# usb-hub-v0_1.net
KiCad netlist of a schematic drawn in EAGLE
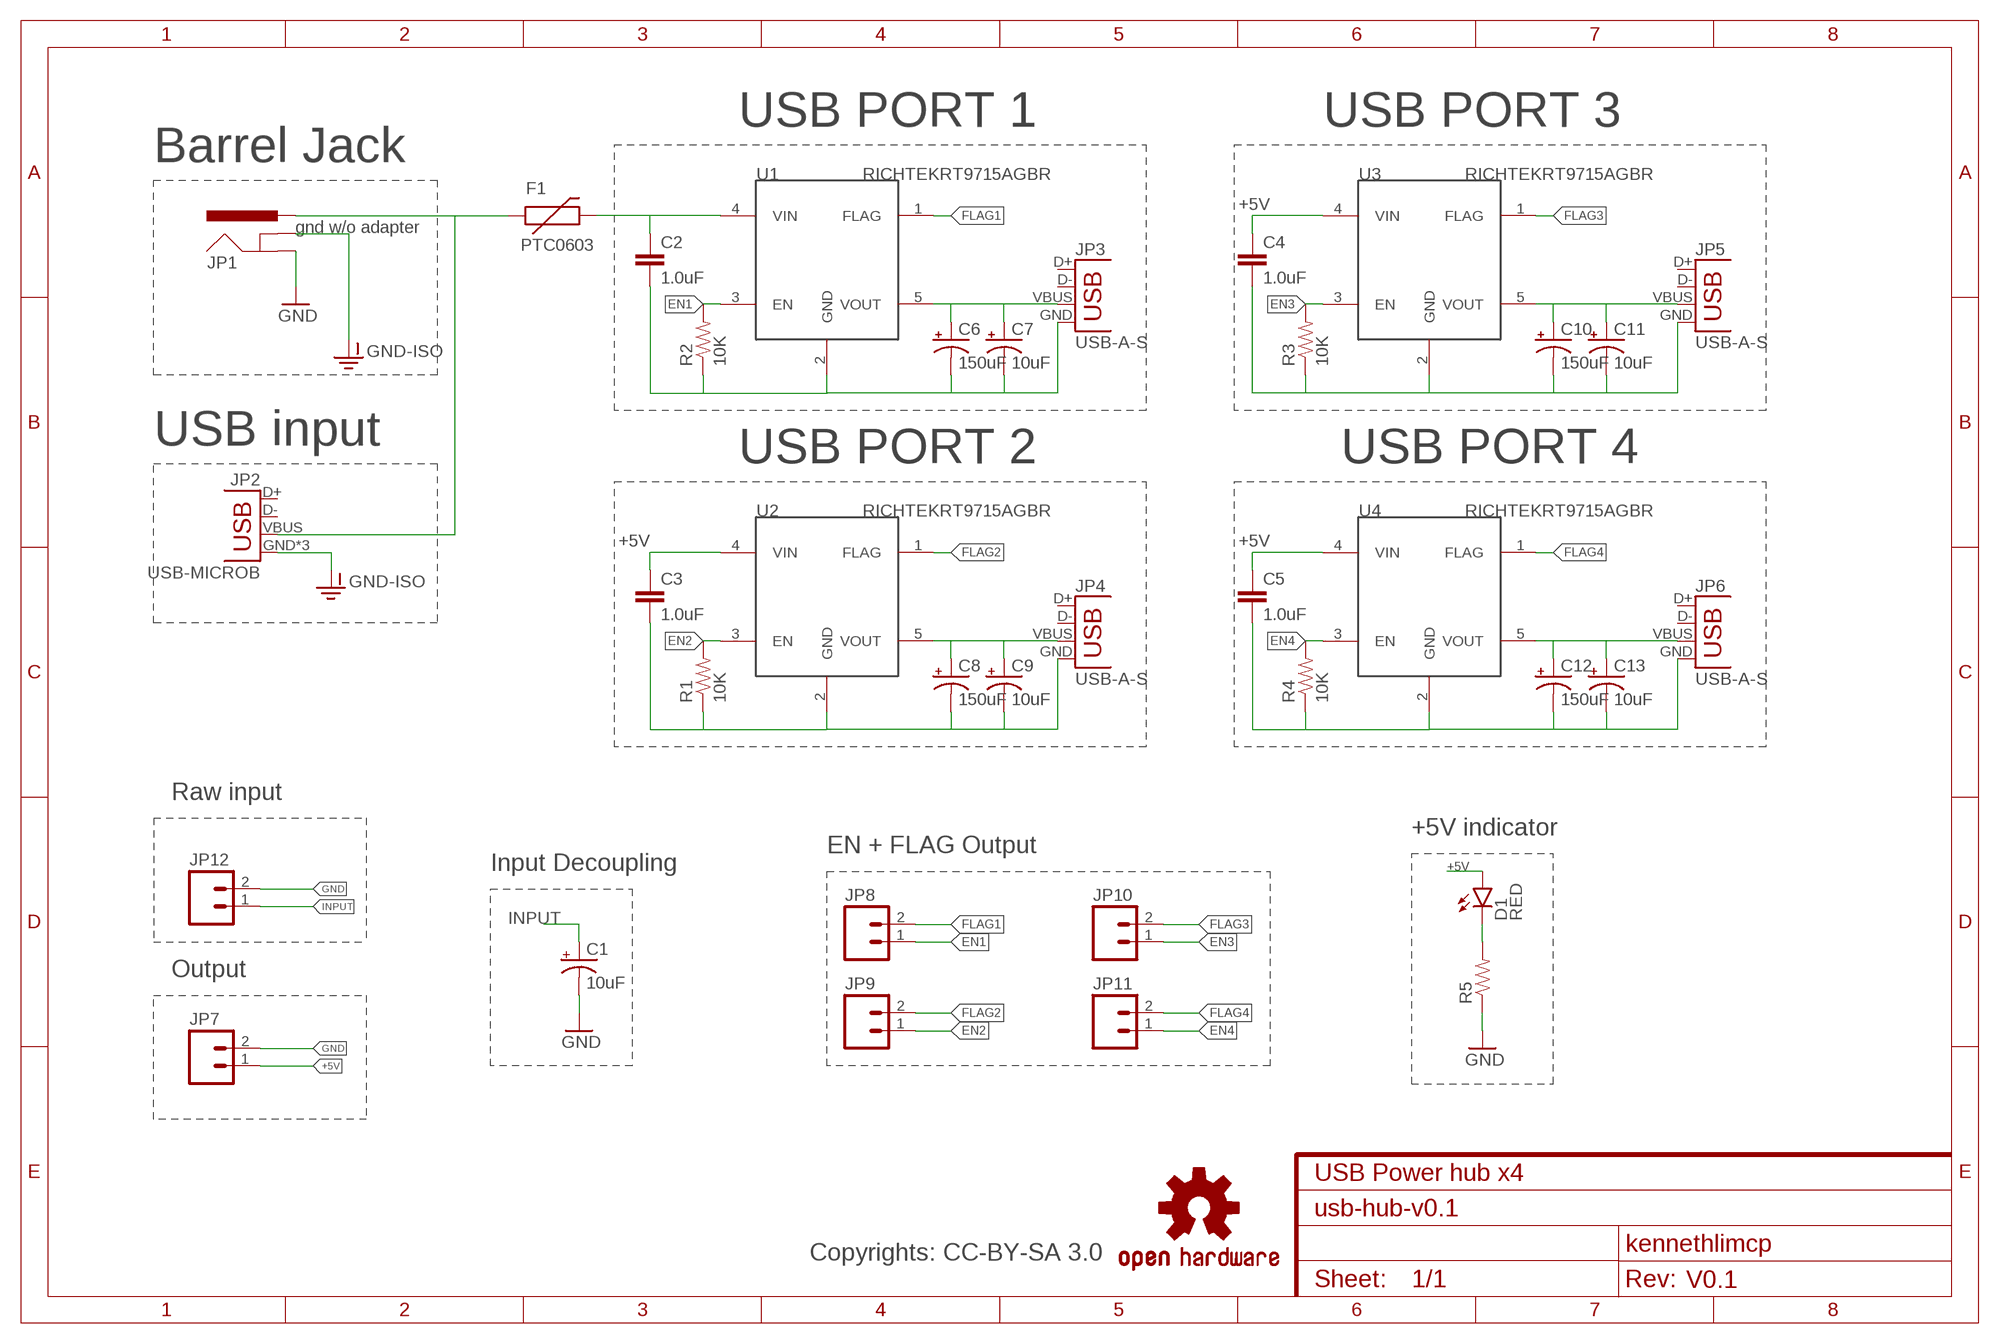
[diagram p0: schematic, sheet 1]

(export (version "E")
  (design (tool "Eeschema 10.0.6"))
  (components
    (comp (ref "C1")
      (value "10uF")
      (footprint "eagle-import:EIA3216")
      (libsource (lib "eagle-import") (part "10UF-16V-10%(TANT)"))
    )
    (comp (ref "C2")
      (value "1.0uF")
      (footprint "eagle-import:0603-CAP")
      (libsource (lib "eagle-import") (part "1.0UF-16V-10%(0603)"))
    )
    (comp (ref "C3")
      (value "1.0uF")
      (footprint "eagle-import:0603-CAP")
      (libsource (lib "eagle-import") (part "1.0UF-16V-10%(0603)"))
    )
    (comp (ref "C4")
      (value "1.0uF")
      (footprint "eagle-import:0603-CAP")
      (libsource (lib "eagle-import") (part "1.0UF-16V-10%(0603)"))
    )
    (comp (ref "C5")
      (value "1.0uF")
      (footprint "eagle-import:0603-CAP")
      (libsource (lib "eagle-import") (part "1.0UF-16V-10%(0603)"))
    )
    (comp (ref "C6")
      (value "150uF")
      (footprint "eagle-import:PANASONIC_D")
      (libsource (lib "eagle-import") (part "CAP_POLD"))
    )
    (comp (ref "C7")
      (value "10uF")
      (footprint "eagle-import:EIA3216")
      (libsource (lib "eagle-import") (part "10UF-16V-10%(TANT)"))
    )
    (comp (ref "C8")
      (value "150uF")
      (footprint "eagle-import:PANASONIC_D")
      (libsource (lib "eagle-import") (part "CAP_POLD"))
    )
    (comp (ref "C9")
      (value "10uF")
      (footprint "eagle-import:EIA3216")
      (libsource (lib "eagle-import") (part "10UF-16V-10%(TANT)"))
    )
    (comp (ref "C10")
      (value "150uF")
      (footprint "eagle-import:PANASONIC_D")
      (libsource (lib "eagle-import") (part "CAP_POLD"))
    )
    (comp (ref "C11")
      (value "10uF")
      (footprint "eagle-import:EIA3216")
      (libsource (lib "eagle-import") (part "10UF-16V-10%(TANT)"))
    )
    (comp (ref "C12")
      (value "150uF")
      (footprint "eagle-import:PANASONIC_D")
      (libsource (lib "eagle-import") (part "CAP_POLD"))
    )
    (comp (ref "C13")
      (value "10uF")
      (footprint "eagle-import:EIA3216")
      (libsource (lib "eagle-import") (part "10UF-16V-10%(TANT)"))
    )
    (comp (ref "D1")
      (value "RED")
      (footprint "eagle-import:LED-0603")
      (libsource (lib "eagle-import") (part "LED-RED0603"))
    )
    (comp (ref "F1")
      (value "PTC0603")
      (footprint "eagle-import:0603")
      (libsource (lib "eagle-import") (part "PTC0603"))
    )
    (comp (ref "JP1")
      (value "POWER_JACKPTH_LOCK")
      (footprint "eagle-import:POWER_JACK_PTH_LOCK")
      (libsource (lib "eagle-import") (part "POWER_JACKPTH_LOCK"))
    )
    (comp (ref "JP2")
      (value "USB-MICROB")
      (footprint "eagle-import:USB-MICROB")
      (libsource (lib "eagle-import") (part "USB-MICROB"))
    )
    (comp (ref "JP3")
      (value "USB-A-S")
      (footprint "eagle-import:USB-A-S")
      (libsource (lib "eagle-import") (part "USB-A-S"))
    )
    (comp (ref "JP4")
      (value "USB-A-S")
      (footprint "eagle-import:USB-A-S")
      (libsource (lib "eagle-import") (part "USB-A-S"))
    )
    (comp (ref "JP5")
      (value "USB-A-S")
      (footprint "eagle-import:USB-A-S")
      (libsource (lib "eagle-import") (part "USB-A-S"))
    )
    (comp (ref "JP6")
      (value "USB-A-S")
      (footprint "eagle-import:USB-A-S")
      (libsource (lib "eagle-import") (part "USB-A-S"))
    )
    (comp (ref "JP7")
      (value "M02PTH")
      (footprint "eagle-import:1X02")
      (libsource (lib "eagle-import") (part "M02PTH"))
    )
    (comp (ref "JP8")
      (value "M02PTH")
      (footprint "eagle-import:1X02")
      (libsource (lib "eagle-import") (part "M02PTH"))
    )
    (comp (ref "JP9")
      (value "M02PTH")
      (footprint "eagle-import:1X02")
      (libsource (lib "eagle-import") (part "M02PTH"))
    )
    (comp (ref "JP10")
      (value "M02PTH")
      (footprint "eagle-import:1X02")
      (libsource (lib "eagle-import") (part "M02PTH"))
    )
    (comp (ref "JP11")
      (value "M02PTH")
      (footprint "eagle-import:1X02")
      (libsource (lib "eagle-import") (part "M02PTH"))
    )
    (comp (ref "JP12")
      (value "M02PTH")
      (footprint "eagle-import:1X02")
      (libsource (lib "eagle-import") (part "M02PTH"))
    )
    (comp (ref "LOGO1")
      (value "OSHW-LOGOPAD")
      (footprint "eagle-import:OSHW-LOGO-M-PAD")
      (libsource (lib "eagle-import") (part "OSHW-LOGOPAD"))
    )
    (comp (ref "R1")
      (value "10K")
      (footprint "eagle-import:0402-RES")
      (libsource (lib "eagle-import") (part "RESISTOR0402"))
    )
    (comp (ref "R2")
      (value "10K")
      (footprint "eagle-import:0402-RES")
      (libsource (lib "eagle-import") (part "RESISTOR0402"))
    )
    (comp (ref "R3")
      (value "10K")
      (footprint "eagle-import:0402-RES")
      (libsource (lib "eagle-import") (part "RESISTOR0402"))
    )
    (comp (ref "R4")
      (value "10K")
      (footprint "eagle-import:0402-RES")
      (libsource (lib "eagle-import") (part "RESISTOR0402"))
    )
    (comp (ref "R5")
      (value "RESISTOR0402")
      (footprint "eagle-import:0402-RES")
      (libsource (lib "eagle-import") (part "RESISTOR0402"))
    )
    (comp (ref "U1")
      (value "RICHTEKRT9715AGBR")
      (footprint "eagle-import:SOT23-5")
      (libsource (lib "eagle-import") (part "RICHTEKRT9715AGBR"))
    )
    (comp (ref "U2")
      (value "RICHTEKRT9715AGBR")
      (footprint "eagle-import:SOT23-5")
      (libsource (lib "eagle-import") (part "RICHTEKRT9715AGBR"))
    )
    (comp (ref "U3")
      (value "RICHTEKRT9715AGBR")
      (footprint "eagle-import:SOT23-5")
      (libsource (lib "eagle-import") (part "RICHTEKRT9715AGBR"))
    )
    (comp (ref "U4")
      (value "RICHTEKRT9715AGBR")
      (footprint "eagle-import:SOT23-5")
      (libsource (lib "eagle-import") (part "RICHTEKRT9715AGBR"))
    )
  )
  (nets
    (net (code "1") (name "+5V") (class "Default")
      (node (ref "C2") (pin "1") (pinfunction "1_1") (pintype "passive"))
      (node (ref "C3") (pin "1") (pinfunction "1_1") (pintype "passive"))
      (node (ref "C4") (pin "1") (pinfunction "1_1") (pintype "passive"))
      (node (ref "C5") (pin "1") (pinfunction "1_1") (pintype "passive"))
      (node (ref "D1") (pin "A") (pinfunction "A_A") (pintype "passive"))
      (node (ref "F1") (pin "2") (pinfunction "2_2") (pintype "bidirectional"))
      (node (ref "JP7") (pin "1") (pinfunction "1_1") (pintype "passive"))
      (node (ref "U1") (pin "4") (pinfunction "VIN_4") (pintype "bidirectional"))
      (node (ref "U2") (pin "4") (pinfunction "VIN_4") (pintype "bidirectional"))
      (node (ref "U3") (pin "4") (pinfunction "VIN_4") (pintype "bidirectional"))
      (node (ref "U4") (pin "4") (pinfunction "VIN_4") (pintype "bidirectional"))
    )
    (net (code "2") (name "EN1") (class "Default")
      (node (ref "JP8") (pin "1") (pinfunction "1_1") (pintype "passive"))
      (node (ref "R2") (pin "2") (pinfunction "2_2") (pintype "passive"))
      (node (ref "U1") (pin "3") (pinfunction "EN_3") (pintype "bidirectional"))
    )
    (net (code "3") (name "EN2") (class "Default")
      (node (ref "JP9") (pin "1") (pinfunction "1_1") (pintype "passive"))
      (node (ref "R1") (pin "2") (pinfunction "2_2") (pintype "passive"))
      (node (ref "U2") (pin "3") (pinfunction "EN_3") (pintype "bidirectional"))
    )
    (net (code "4") (name "EN3") (class "Default")
      (node (ref "JP10") (pin "1") (pinfunction "1_1") (pintype "passive"))
      (node (ref "R3") (pin "2") (pinfunction "2_2") (pintype "passive"))
      (node (ref "U3") (pin "3") (pinfunction "EN_3") (pintype "bidirectional"))
    )
    (net (code "5") (name "EN4") (class "Default")
      (node (ref "JP11") (pin "1") (pinfunction "1_1") (pintype "passive"))
      (node (ref "R4") (pin "2") (pinfunction "2_2") (pintype "passive"))
      (node (ref "U4") (pin "3") (pinfunction "EN_3") (pintype "bidirectional"))
    )
    (net (code "6") (name "FLAG1") (class "Default")
      (node (ref "JP8") (pin "2") (pinfunction "2_2") (pintype "passive"))
      (node (ref "U1") (pin "1") (pinfunction "FLAG_1") (pintype "bidirectional"))
    )
    (net (code "7") (name "FLAG2") (class "Default")
      (node (ref "JP9") (pin "2") (pinfunction "2_2") (pintype "passive"))
      (node (ref "U2") (pin "1") (pinfunction "FLAG_1") (pintype "bidirectional"))
    )
    (net (code "8") (name "FLAG3") (class "Default")
      (node (ref "JP10") (pin "2") (pinfunction "2_2") (pintype "passive"))
      (node (ref "U3") (pin "1") (pinfunction "FLAG_1") (pintype "bidirectional"))
    )
    (net (code "9") (name "FLAG4") (class "Default")
      (node (ref "JP11") (pin "2") (pinfunction "2_2") (pintype "passive"))
      (node (ref "U4") (pin "1") (pinfunction "FLAG_1") (pintype "bidirectional"))
    )
    (net (code "10") (name "GND") (class "Default")
      (node (ref "C1") (pin "C") (pinfunction "-_C") (pintype "passive"))
      (node (ref "C10") (pin "-") (pinfunction "-_-") (pintype "passive"))
      (node (ref "C11") (pin "C") (pinfunction "-_C") (pintype "passive"))
      (node (ref "C12") (pin "-") (pinfunction "-_-") (pintype "passive"))
      (node (ref "C13") (pin "C") (pinfunction "-_C") (pintype "passive"))
      (node (ref "C2") (pin "2") (pinfunction "2_2") (pintype "passive"))
      (node (ref "C3") (pin "2") (pinfunction "2_2") (pintype "passive"))
      (node (ref "C4") (pin "2") (pinfunction "2_2") (pintype "passive"))
      (node (ref "C5") (pin "2") (pinfunction "2_2") (pintype "passive"))
      (node (ref "C6") (pin "-") (pinfunction "-_-") (pintype "passive"))
      (node (ref "C7") (pin "C") (pinfunction "-_C") (pintype "passive"))
      (node (ref "C8") (pin "-") (pinfunction "-_-") (pintype "passive"))
      (node (ref "C9") (pin "C") (pinfunction "-_C") (pintype "passive"))
      (node (ref "JP1") (pin "GND") (pinfunction "GND_GND") (pintype "bidirectional"))
      (node (ref "JP12") (pin "2") (pinfunction "2_2") (pintype "passive"))
      (node (ref "JP3") (pin "GND") (pinfunction "GND_GND") (pintype "bidirectional"))
      (node (ref "JP4") (pin "GND") (pinfunction "GND_GND") (pintype "bidirectional"))
      (node (ref "JP5") (pin "GND") (pinfunction "GND_GND") (pintype "bidirectional"))
      (node (ref "JP6") (pin "GND") (pinfunction "GND_GND") (pintype "bidirectional"))
      (node (ref "JP7") (pin "2") (pinfunction "2_2") (pintype "passive"))
      (node (ref "R1") (pin "1") (pinfunction "1_1") (pintype "passive"))
      (node (ref "R2") (pin "1") (pinfunction "1_1") (pintype "passive"))
      (node (ref "R3") (pin "1") (pinfunction "1_1") (pintype "passive"))
      (node (ref "R4") (pin "1") (pinfunction "1_1") (pintype "passive"))
      (node (ref "R5") (pin "1") (pinfunction "1_1") (pintype "passive"))
      (node (ref "U1") (pin "2") (pinfunction "GND_2") (pintype "bidirectional"))
      (node (ref "U2") (pin "2") (pinfunction "GND_2") (pintype "bidirectional"))
      (node (ref "U3") (pin "2") (pinfunction "GND_2") (pintype "bidirectional"))
      (node (ref "U4") (pin "2") (pinfunction "GND_2") (pintype "bidirectional"))
    )
    (net (code "11") (name "GND-ISO") (class "Default")
      (node (ref "JP1") (pin "GNDBREAK") (pinfunction "GNDBREAK_GNDBREAK") (pintype "bidirectional"))
      (node (ref "JP2") (pin "GND") (pinfunction "GND_GND") (pintype "bidirectional"))
      (node (ref "JP2") (pin "MT1") (pinfunction "GND_MT1") (pintype "bidirectional"))
      (node (ref "JP2") (pin "MT2") (pinfunction "GND_MT2") (pintype "bidirectional"))
    )
    (net (code "12") (name "INPUT") (class "Default")
      (node (ref "C1") (pin "A") (pinfunction "+_A") (pintype "passive"))
      (node (ref "F1") (pin "1") (pinfunction "1_1") (pintype "bidirectional"))
      (node (ref "JP1") (pin "PWR") (pinfunction "PWR_PWR") (pintype "bidirectional"))
      (node (ref "JP12") (pin "1") (pinfunction "1_1") (pintype "passive"))
      (node (ref "JP2") (pin "VBUS") (pinfunction "VBUS_VBUS") (pintype "bidirectional"))
    )
    (net (code "13") (name "Net-(C7-+)") (class "Default")
      (node (ref "C6") (pin "+") (pinfunction "+_+") (pintype "passive"))
      (node (ref "C7") (pin "A") (pinfunction "+_A") (pintype "passive"))
      (node (ref "JP3") (pin "VBUS") (pinfunction "VBUS_VBUS") (pintype "bidirectional"))
      (node (ref "U1") (pin "5") (pinfunction "VOUT_5") (pintype "bidirectional"))
    )
    (net (code "14") (name "Net-(C9-+)") (class "Default")
      (node (ref "C8") (pin "+") (pinfunction "+_+") (pintype "passive"))
      (node (ref "C9") (pin "A") (pinfunction "+_A") (pintype "passive"))
      (node (ref "JP4") (pin "VBUS") (pinfunction "VBUS_VBUS") (pintype "bidirectional"))
      (node (ref "U2") (pin "5") (pinfunction "VOUT_5") (pintype "bidirectional"))
    )
    (net (code "15") (name "Net-(C11-+)") (class "Default")
      (node (ref "C10") (pin "+") (pinfunction "+_+") (pintype "passive"))
      (node (ref "C11") (pin "A") (pinfunction "+_A") (pintype "passive"))
      (node (ref "JP5") (pin "VBUS") (pinfunction "VBUS_VBUS") (pintype "bidirectional"))
      (node (ref "U3") (pin "5") (pinfunction "VOUT_5") (pintype "bidirectional"))
    )
    (net (code "16") (name "Net-(C13-+)") (class "Default")
      (node (ref "C12") (pin "+") (pinfunction "+_+") (pintype "passive"))
      (node (ref "C13") (pin "A") (pinfunction "+_A") (pintype "passive"))
      (node (ref "JP6") (pin "VBUS") (pinfunction "VBUS_VBUS") (pintype "bidirectional"))
      (node (ref "U4") (pin "5") (pinfunction "VOUT_5") (pintype "bidirectional"))
    )
    (net (code "17") (name "Net-(D1-PadC)") (class "Default")
      (node (ref "D1") (pin "C") (pinfunction "C_C") (pintype "passive"))
      (node (ref "R5") (pin "2") (pinfunction "2_2") (pintype "passive"))
    )
    (net (code "18") (name "unconnected-(JP2-PadD+)") (class "Default")
      (node (ref "JP2") (pin "D+") (pinfunction "D+_D+") (pintype "bidirectional"))
    )
    (net (code "19") (name "unconnected-(JP2-PadD-)") (class "Default")
      (node (ref "JP2") (pin "D-") (pinfunction "D-_D-") (pintype "bidirectional"))
    )
    (net (code "20") (name "unconnected-(JP3-PadD+)") (class "Default")
      (node (ref "JP3") (pin "D+") (pinfunction "D+_D+") (pintype "bidirectional"))
    )
    (net (code "21") (name "unconnected-(JP3-PadD-)") (class "Default")
      (node (ref "JP3") (pin "D-") (pinfunction "D-_D-") (pintype "bidirectional"))
    )
    (net (code "22") (name "unconnected-(JP4-PadD+)") (class "Default")
      (node (ref "JP4") (pin "D+") (pinfunction "D+_D+") (pintype "bidirectional"))
    )
    (net (code "23") (name "unconnected-(JP4-PadD-)") (class "Default")
      (node (ref "JP4") (pin "D-") (pinfunction "D-_D-") (pintype "bidirectional"))
    )
    (net (code "24") (name "unconnected-(JP5-PadD+)") (class "Default")
      (node (ref "JP5") (pin "D+") (pinfunction "D+_D+") (pintype "bidirectional"))
    )
    (net (code "25") (name "unconnected-(JP5-PadD-)") (class "Default")
      (node (ref "JP5") (pin "D-") (pinfunction "D-_D-") (pintype "bidirectional"))
    )
    (net (code "26") (name "unconnected-(JP6-PadD+)") (class "Default")
      (node (ref "JP6") (pin "D+") (pinfunction "D+_D+") (pintype "bidirectional"))
    )
    (net (code "27") (name "unconnected-(JP6-PadD-)") (class "Default")
      (node (ref "JP6") (pin "D-") (pinfunction "D-_D-") (pintype "bidirectional"))
    )
  )
)
